# Transient_tester_r2B1.net
KiCad netlist of a schematic drawn in EAGLE
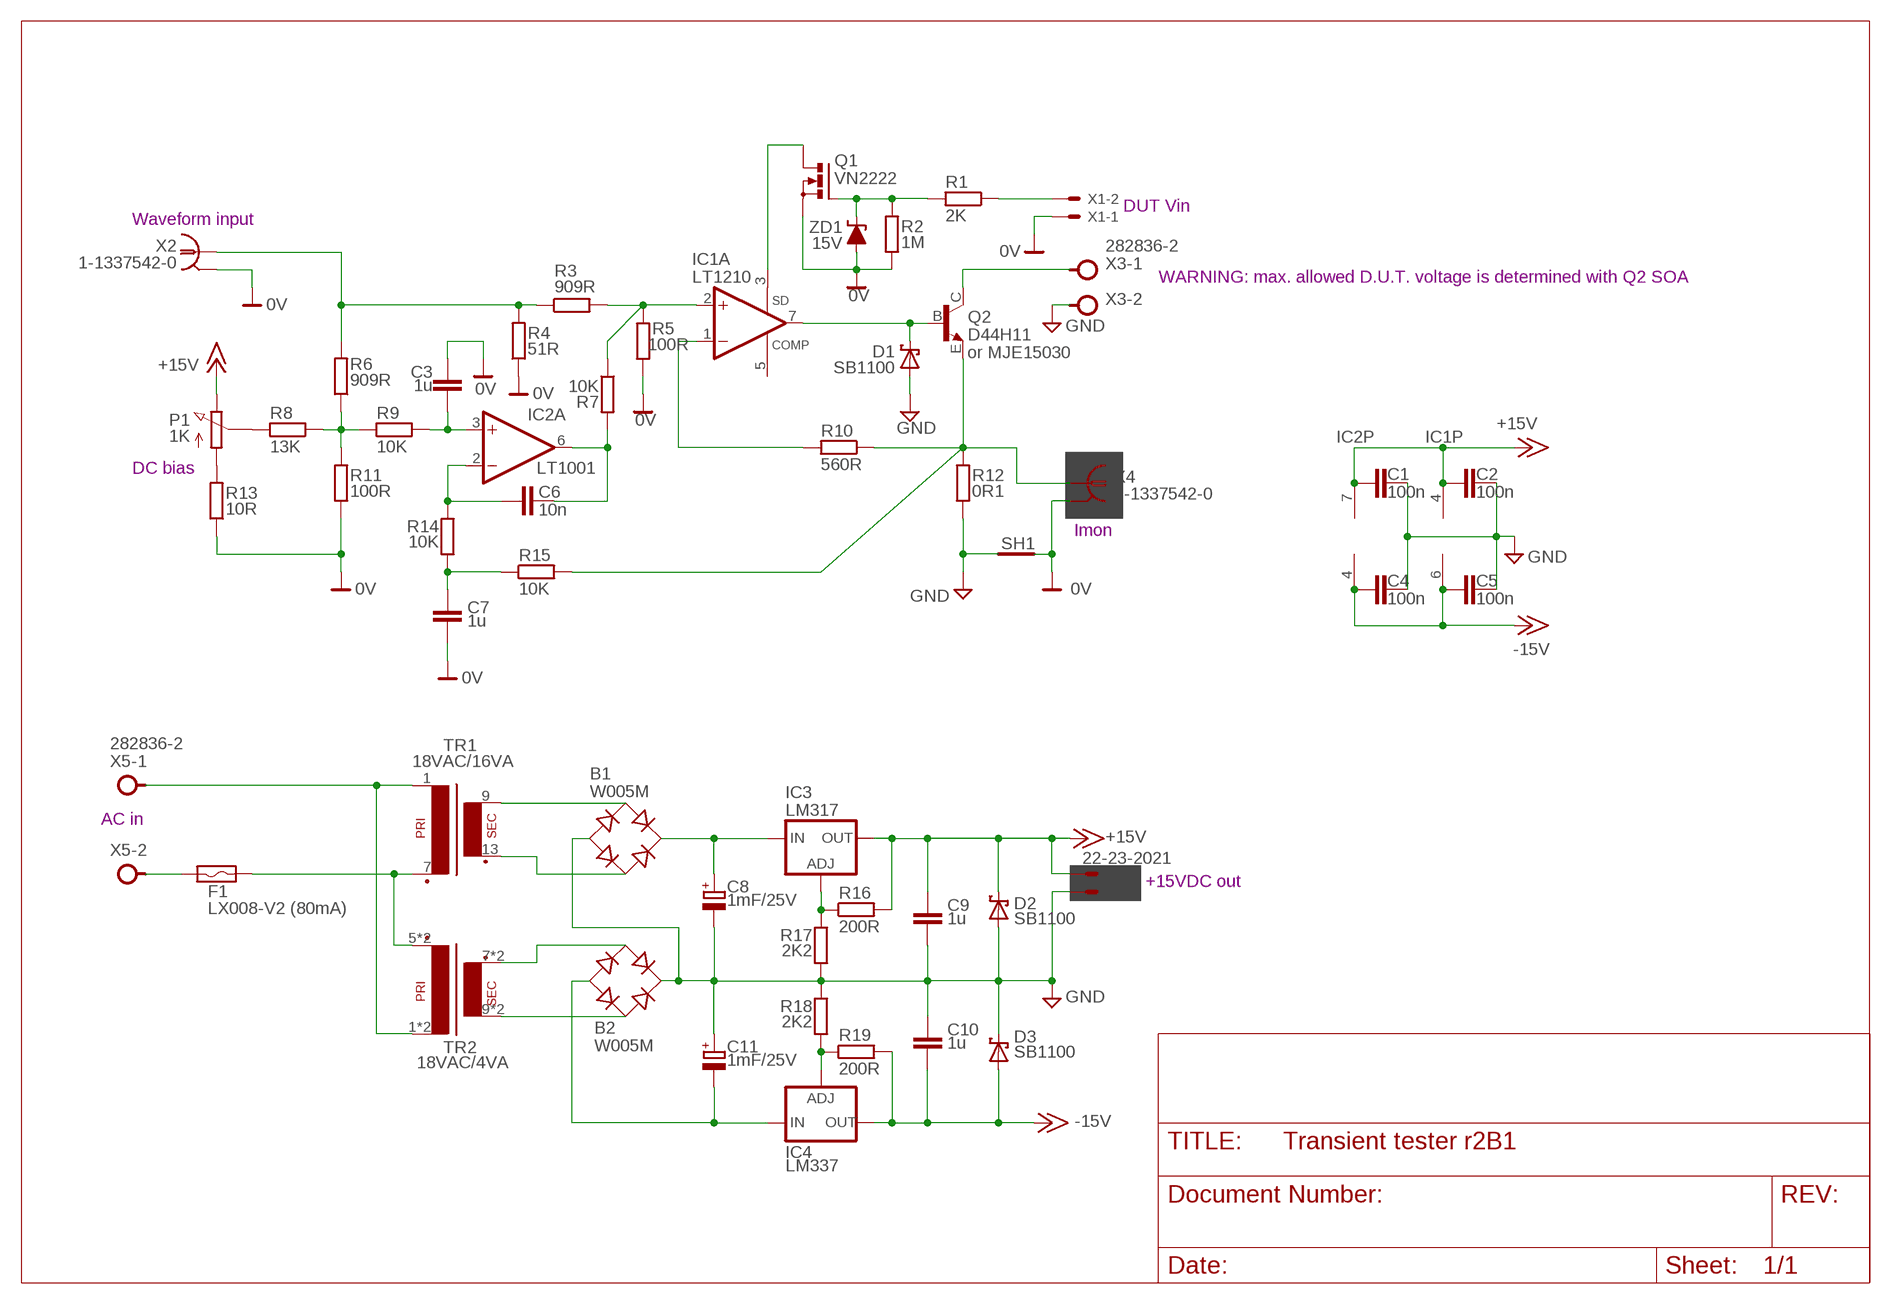
[diagram p0: schematic, sheet 1]

(export (version "E")
  (design (tool "Eeschema 10.0.6"))
  (components
    (comp (ref "B1")
      (value "W005M")
      (footprint "eagle-import:RB1A")
      (libsource (lib "eagle-import") (part "RECTIFIER-RB1A"))
    )
    (comp (ref "B2")
      (value "W005M")
      (footprint "eagle-import:RB1A")
      (libsource (lib "eagle-import") (part "RECTIFIER-RB1A"))
    )
    (comp (ref "C1")
      (value "100n")
      (footprint "eagle-import:C050-025X075")
      (libsource (lib "eagle-import") (part "C-EU050-025X075"))
    )
    (comp (ref "C2")
      (value "100n")
      (footprint "eagle-import:C050-025X075")
      (libsource (lib "eagle-import") (part "C-EU050-025X075"))
    )
    (comp (ref "C3")
      (value "1u")
      (footprint "eagle-import:C050-075X075")
      (libsource (lib "eagle-import") (part "C-EU050-075X075"))
    )
    (comp (ref "C4")
      (value "100n")
      (footprint "eagle-import:C050-025X075")
      (libsource (lib "eagle-import") (part "C-EU050-025X075"))
    )
    (comp (ref "C5")
      (value "100n")
      (footprint "eagle-import:C050-025X075")
      (libsource (lib "eagle-import") (part "C-EU050-025X075"))
    )
    (comp (ref "C6")
      (value "10n")
      (footprint "eagle-import:C050-025X075")
      (libsource (lib "eagle-import") (part "C-EU050-025X075"))
    )
    (comp (ref "C7")
      (value "1u")
      (footprint "eagle-import:C050-075X075")
      (libsource (lib "eagle-import") (part "C-EU050-075X075"))
    )
    (comp (ref "C8")
      (value "1mF/25V")
      (footprint "eagle-import:ECAP5_10.5")
      (libsource (lib "eagle-import") (part "ECAP5G_10.5MM"))
    )
    (comp (ref "C9")
      (value "1u")
      (footprint "eagle-import:C050-025X075")
      (libsource (lib "eagle-import") (part "C-EU050-025X075"))
    )
    (comp (ref "C10")
      (value "1u")
      (footprint "eagle-import:C050-025X075")
      (libsource (lib "eagle-import") (part "C-EU050-025X075"))
    )
    (comp (ref "C11")
      (value "1mF/25V")
      (footprint "eagle-import:ECAP5_10.5")
      (libsource (lib "eagle-import") (part "ECAP5G_10.5MM"))
    )
    (comp (ref "D1")
      (value "SB1100")
      (footprint "eagle-import:DO34_10")
      (libsource (lib "eagle-import") (part "SCHOTTKY"))
    )
    (comp (ref "D2")
      (value "SB1100")
      (footprint "eagle-import:DO34_10")
      (libsource (lib "eagle-import") (part "SCHOTTKY"))
    )
    (comp (ref "D3")
      (value "SB1100")
      (footprint "eagle-import:DO34_10")
      (libsource (lib "eagle-import") (part "SCHOTTKY"))
    )
    (comp (ref "F1")
      (value "LX008-V2 (80mA)")
      (footprint "eagle-import:POLYSWITCH-R7")
      (libsource (lib "eagle-import") (part "FUSE_RESETTABLER7"))
    )
    (comp (ref "IC1")
      (value "LT1210")
      (footprint "eagle-import:TO220-7")
      (libsource (lib "eagle-import") (part "LT1210"))
    )
    (comp (ref "IC2")
      (value "LT1001")
      (footprint "eagle-import:DIL08D")
      (libsource (lib "eagle-import") (part "LT1001"))
    )
    (comp (ref "IC3")
      (value "LM317")
      (footprint "eagle-import:317TS")
      (libsource (lib "eagle-import") (part "LM317TS"))
    )
    (comp (ref "IC4")
      (value "LM337")
      (footprint "eagle-import:337TS")
      (libsource (lib "eagle-import") (part "LM337TS"))
    )
    (comp (ref "P1")
      (value "1K")
      (footprint "eagle-import:BOURNS_POT91")
      (libsource (lib "eagle-import") (part "POTENTIOMETER"))
    )
    (comp (ref "Q1")
      (value "VN2222")
      (footprint "eagle-import:TO92-SGD")
      (libsource (lib "eagle-import") (part "2N7000"))
    )
    (comp (ref "Q2")
      (value "D44H11")
      (footprint "eagle-import:TO220BV")
      (libsource (lib "eagle-import") (part "D44H11"))
    )
    (comp (ref "R1")
      (value "2K")
      (footprint "eagle-import:0204_5")
      (libsource (lib "eagle-import") (part "R-EU_0204/5"))
    )
    (comp (ref "R2")
      (value "1M")
      (footprint "eagle-import:0204_5")
      (libsource (lib "eagle-import") (part "R-EU_0204/5"))
    )
    (comp (ref "R3")
      (value "909R")
      (footprint "eagle-import:0207_10")
      (libsource (lib "eagle-import") (part "R-EU_0207/10"))
    )
    (comp (ref "R4")
      (value "51R")
      (footprint "eagle-import:0204_5")
      (libsource (lib "eagle-import") (part "R-EU_0204/5"))
    )
    (comp (ref "R5")
      (value "100R")
      (footprint "eagle-import:0204_5")
      (libsource (lib "eagle-import") (part "R-EU_0204/5"))
    )
    (comp (ref "R6")
      (value "909R")
      (footprint "eagle-import:0207_10")
      (libsource (lib "eagle-import") (part "R-EU_0207/10"))
    )
    (comp (ref "R7")
      (value "10K")
      (footprint "eagle-import:0204_5")
      (libsource (lib "eagle-import") (part "R-EU_0204/5"))
    )
    (comp (ref "R8")
      (value "13K")
      (footprint "eagle-import:0204_5")
      (libsource (lib "eagle-import") (part "R-EU_0204/5"))
    )
    (comp (ref "R9")
      (value "10K")
      (footprint "eagle-import:0204_5")
      (libsource (lib "eagle-import") (part "R-EU_0204/5"))
    )
    (comp (ref "R10")
      (value "560R")
      (footprint "eagle-import:0204_5")
      (libsource (lib "eagle-import") (part "R-EU_0204/5"))
    )
    (comp (ref "R11")
      (value "100R")
      (footprint "eagle-import:0204_5")
      (libsource (lib "eagle-import") (part "R-EU_0204/5"))
    )
    (comp (ref "R12")
      (value "0R1")
      (footprint "eagle-import:OAR1+2512")
      (libsource (lib "eagle-import") (part "R_EU_OAR1+2512"))
    )
    (comp (ref "R13")
      (value "10R")
      (footprint "eagle-import:0204_5")
      (libsource (lib "eagle-import") (part "R-EU_0204/5"))
    )
    (comp (ref "R14")
      (value "10K")
      (footprint "eagle-import:0204_5")
      (libsource (lib "eagle-import") (part "R-EU_0204/5"))
    )
    (comp (ref "R15")
      (value "10K")
      (footprint "eagle-import:0204_5")
      (libsource (lib "eagle-import") (part "R-EU_0204/5"))
    )
    (comp (ref "R16")
      (value "200R")
      (footprint "eagle-import:0204_5")
      (libsource (lib "eagle-import") (part "R-EU_0204/5"))
    )
    (comp (ref "R17")
      (value "2K2")
      (footprint "eagle-import:0204_5")
      (libsource (lib "eagle-import") (part "R-EU_0204/5"))
    )
    (comp (ref "R18")
      (value "2K2")
      (footprint "eagle-import:0204_5")
      (libsource (lib "eagle-import") (part "R-EU_0204/5"))
    )
    (comp (ref "R19")
      (value "200R")
      (footprint "eagle-import:0204_5")
      (libsource (lib "eagle-import") (part "R-EU_0204/5"))
    )
    (comp (ref "SH1")
      (value "SHORTH")
      (footprint "eagle-import:SHORT_2")
      (libsource (lib "eagle-import") (part "SHORTH"))
    )
    (comp (ref "TR1")
      (value "18VAC/16VA")
      (footprint "eagle-import:PCB_TRAFO16VA")
      (libsource (lib "eagle-import") (part "PCB_TRAFO16VA"))
    )
    (comp (ref "TR2")
      (value "18VAC/4VA")
      (footprint "eagle-import:PCB_TRAFO_4VA")
      (libsource (lib "eagle-import") (part "PCB_TRAFO4VA"))
    )
    (comp (ref "X1")
      (value "22-23-2021")
      (footprint "eagle-import:22-23-2021")
      (fields (field (name "MF") "MOLEX"))
      (libsource (lib "eagle-import") (part "22-23-2021"))
    )
    (comp (ref "X2")
      (value "1-1337542-0")
      (footprint "eagle-import:AMP_227161")
      (fields (field (name "MF") "TYCO ELECTRONICS") (field (name "MPN") "1-227161"))
      (libsource (lib "eagle-import") (part "?2271611--0"))
    )
    (comp (ref "X3")
      (value "282836-2")
      (footprint "eagle-import:TBLOCK5.0_2")
      (libsource (lib "eagle-import") (part "TBLOCK5.0_2A"))
    )
    (comp (ref "X4")
      (value "1-1337542-0")
      (footprint "eagle-import:AMP_227161")
      (fields (field (name "MF") "TYCO ELECTRONICS") (field (name "MPN") "1-227161"))
      (libsource (lib "eagle-import") (part "?2271611--0"))
    )
    (comp (ref "X5")
      (value "282836-2")
      (footprint "eagle-import:TBLOCK5.0_2")
      (libsource (lib "eagle-import") (part "TBLOCK5.0_2A"))
    )
    (comp (ref "X6")
      (value "22-23-2021")
      (footprint "eagle-import:22-23-2021")
      (fields
        (field (name "MF") "MOLEX")
        (field (name "MF_1") "MOLEX")
        (field (name "MPN") "22-23-2021")
        (field (name "OC_FARNELL") "1462926")
        (field (name "OC_NEWARK") "25C3832")
      )
      (libsource (lib "eagle-import") (part "22-23-2021"))
    )
    (comp (ref "ZD1")
      (value "15V")
      (footprint "eagle-import:DO34-ZD")
      (libsource (lib "eagle-import") (part "ZENER-DIODE"))
    )
  )
  (nets
    (net (code "1") (name "+15V") (class "Default")
      (node (ref "C1") (pin "2") (pinfunction "2_2") (pintype "passive"))
      (node (ref "C2") (pin "2") (pinfunction "2_2") (pintype "passive"))
      (node (ref "C9") (pin "1") (pinfunction "1_1") (pintype "passive"))
      (node (ref "D2") (pin "C") (pinfunction "C_C") (pintype "passive"))
      (node (ref "IC1") (pin "4") (pinfunction "V+_4") (pintype "power_in"))
      (node (ref "IC2") (pin "7") (pinfunction "V+_7") (pintype "power_in"))
      (node (ref "IC3") (pin "2") (pinfunction "OUT_2") (pintype "passive"))
      (node (ref "P1") (pin "1") (pinfunction "E_1") (pintype "passive"))
      (node (ref "R16") (pin "2") (pinfunction "2_2") (pintype "passive"))
      (node (ref "X6") (pin "1") (pinfunction "S_1") (pintype "passive"))
    )
    (net (code "2") (name "-15V") (class "Default")
      (node (ref "C10") (pin "2") (pinfunction "2_2") (pintype "passive"))
      (node (ref "C4") (pin "2") (pinfunction "2_2") (pintype "passive"))
      (node (ref "C5") (pin "2") (pinfunction "2_2") (pintype "passive"))
      (node (ref "D3") (pin "A") (pinfunction "A_A") (pintype "passive"))
      (node (ref "IC1") (pin "6") (pinfunction "V-_6") (pintype "power_in"))
      (node (ref "IC2") (pin "4") (pinfunction "V-_4") (pintype "power_in"))
      (node (ref "IC4") (pin "3") (pinfunction "OUT_3") (pintype "passive"))
      (node (ref "R19") (pin "2") (pinfunction "2_2") (pintype "passive"))
    )
    (net (code "3") (name "0V") (class "Default")
      (node (ref "C3") (pin "1") (pinfunction "1_1") (pintype "passive"))
      (node (ref "C7") (pin "2") (pinfunction "2_2") (pintype "passive"))
      (node (ref "Q1") (pin "S") (pinfunction "S_S") (pintype "passive"))
      (node (ref "R11") (pin "1") (pinfunction "1_1") (pintype "passive"))
      (node (ref "R13") (pin "1") (pinfunction "1_1") (pintype "passive"))
      (node (ref "R2") (pin "1") (pinfunction "1_1") (pintype "passive"))
      (node (ref "R4") (pin "1") (pinfunction "1_1") (pintype "passive"))
      (node (ref "R5") (pin "2") (pinfunction "2_2") (pintype "passive"))
      (node (ref "SH1") (pin "2") (pinfunction "GND_B_2") (pintype "bidirectional"))
      (node (ref "X1") (pin "1") (pinfunction "S_1") (pintype "passive"))
      (node (ref "X2") (pin "2") (pinfunction "GND_2") (pintype "power_in"))
      (node (ref "X4") (pin "2") (pinfunction "GND_2") (pintype "power_in"))
      (node (ref "ZD1") (pin "A") (pinfunction "A_A") (pintype "passive"))
    )
    (net (code "4") (name "GND") (class "Default")
      (node (ref "B1") (pin "-") (pinfunction "-_-") (pintype "passive"))
      (node (ref "B2") (pin "+") (pinfunction "+_+") (pintype "passive"))
      (node (ref "C1") (pin "1") (pinfunction "1_1") (pintype "passive"))
      (node (ref "C10") (pin "1") (pinfunction "1_1") (pintype "passive"))
      (node (ref "C11") (pin "+") (pinfunction "+_+") (pintype "passive"))
      (node (ref "C2") (pin "1") (pinfunction "1_1") (pintype "passive"))
      (node (ref "C4") (pin "1") (pinfunction "1_1") (pintype "passive"))
      (node (ref "C5") (pin "1") (pinfunction "1_1") (pintype "passive"))
      (node (ref "C8") (pin "-") (pinfunction "-_-") (pintype "passive"))
      (node (ref "C9") (pin "2") (pinfunction "2_2") (pintype "passive"))
      (node (ref "D1") (pin "A") (pinfunction "A_A") (pintype "passive"))
      (node (ref "D2") (pin "A") (pinfunction "A_A") (pintype "passive"))
      (node (ref "D3") (pin "C") (pinfunction "C_C") (pintype "passive"))
      (node (ref "R12") (pin "1") (pinfunction "1_1") (pintype "passive"))
      (node (ref "R12") (pin "1.1") (pinfunction "1_1.1") (pintype "passive"))
      (node (ref "R17") (pin "2") (pinfunction "2_2") (pintype "passive"))
      (node (ref "R18") (pin "1") (pinfunction "1_1") (pintype "passive"))
      (node (ref "SH1") (pin "1") (pinfunction "GND_A_1") (pintype "bidirectional"))
      (node (ref "X3") (pin "2") (pinfunction "1_2") (pintype "bidirectional"))
      (node (ref "X6") (pin "2") (pinfunction "S_2") (pintype "passive"))
    )
    (net (code "5") (name "Net-(B2-PadAC1)") (class "Default")
      (node (ref "B2") (pin "AC1") (pinfunction "AC1_AC1") (pintype "passive"))
      (node (ref "TR2") (pin "7") (pinfunction "S2_7") (pintype "passive"))
      (node (ref "TR2") (pin "7.1") (pinfunction "S2_7.1") (pintype "passive"))
    )
    (net (code "6") (name "Net-(B2-PadAC2)") (class "Default")
      (node (ref "B2") (pin "AC2") (pinfunction "AC2_AC2") (pintype "passive"))
      (node (ref "TR2") (pin "9") (pinfunction "S1_9") (pintype "passive"))
      (node (ref "TR2") (pin "9.1") (pinfunction "S1_9.1") (pintype "passive"))
    )
    (net (code "7") (name "Net-(C7-Pad1)") (class "Default")
      (node (ref "C7") (pin "1") (pinfunction "1_1") (pintype "passive"))
      (node (ref "R14") (pin "2") (pinfunction "2_2") (pintype "passive"))
      (node (ref "R15") (pin "1") (pinfunction "1_1") (pintype "passive"))
    )
    (net (code "8") (name "Net-(F1-1)") (class "Default")
      (node (ref "F1") (pin "P$1") (pinfunction "1_P$1") (pintype "passive"))
      (node (ref "X5") (pin "2") (pinfunction "1_2") (pintype "bidirectional"))
    )
    (net (code "9") (name "Net-(F1-2)") (class "Default")
      (node (ref "F1") (pin "P$2") (pinfunction "2_P$2") (pintype "passive"))
      (node (ref "TR1") (pin "7") (pinfunction "P2_7") (pintype "passive"))
      (node (ref "TR2") (pin "5") (pinfunction "P2_5") (pintype "passive"))
      (node (ref "TR2") (pin "5.1") (pinfunction "P2_5.1") (pintype "passive"))
    )
    (net (code "10") (name "Net-(IC1A-+IN)") (class "Default")
      (node (ref "IC1") (pin "2") (pinfunction "+IN_2") (pintype "input"))
      (node (ref "R3") (pin "2") (pinfunction "2_2") (pintype "passive"))
      (node (ref "R5") (pin "1") (pinfunction "1_1") (pintype "passive"))
      (node (ref "R7") (pin "1") (pinfunction "1_1") (pintype "passive"))
    )
    (net (code "11") (name "Net-(IC1A--IN)") (class "Default")
      (node (ref "IC1") (pin "1") (pinfunction "-IN_1") (pintype "input"))
      (node (ref "R10") (pin "2") (pinfunction "2_2") (pintype "passive"))
    )
    (net (code "12") (name "Net-(IC1A-OUT)") (class "Default")
      (node (ref "D1") (pin "C") (pinfunction "C_C") (pintype "passive"))
      (node (ref "IC1") (pin "7") (pinfunction "OUT_7") (pintype "output"))
      (node (ref "Q2") (pin "B") (pinfunction "B_B") (pintype "passive"))
    )
    (net (code "13") (name "Net-(IC1A-SD)") (class "Default")
      (node (ref "IC1") (pin "3") (pinfunction "SD_3") (pintype "input"))
      (node (ref "Q1") (pin "D") (pinfunction "D_D") (pintype "passive"))
    )
    (net (code "14") (name "Net-(IC2A-+IN)") (class "Default")
      (node (ref "C3") (pin "2") (pinfunction "2_2") (pintype "passive"))
      (node (ref "IC2") (pin "3") (pinfunction "+IN_3") (pintype "input"))
      (node (ref "R9") (pin "2") (pinfunction "2_2") (pintype "passive"))
    )
    (net (code "15") (name "Net-(IC2A--IN)") (class "Default")
      (node (ref "C6") (pin "2") (pinfunction "2_2") (pintype "passive"))
      (node (ref "IC2") (pin "2") (pinfunction "-IN_2") (pintype "input"))
      (node (ref "R14") (pin "1") (pinfunction "1_1") (pintype "passive"))
    )
    (net (code "16") (name "Net-(IC2A-OUT)") (class "Default")
      (node (ref "C6") (pin "1") (pinfunction "1_1") (pintype "passive"))
      (node (ref "IC2") (pin "6") (pinfunction "OUT_6") (pintype "output"))
      (node (ref "R7") (pin "2") (pinfunction "2_2") (pintype "passive"))
    )
    (net (code "17") (name "Net-(IC3-ADJ)") (class "Default")
      (node (ref "IC3") (pin "1") (pinfunction "ADJ_1") (pintype "input"))
      (node (ref "R16") (pin "1") (pinfunction "1_1") (pintype "passive"))
      (node (ref "R17") (pin "1") (pinfunction "1_1") (pintype "passive"))
    )
    (net (code "18") (name "Net-(IC3-IN)") (class "Default")
      (node (ref "B1") (pin "+") (pinfunction "+_+") (pintype "passive"))
      (node (ref "C8") (pin "+") (pinfunction "+_+") (pintype "passive"))
      (node (ref "IC3") (pin "3") (pinfunction "IN_3") (pintype "input"))
    )
    (net (code "19") (name "Net-(IC4-ADJ)") (class "Default")
      (node (ref "IC4") (pin "1") (pinfunction "ADJ_1") (pintype "input"))
      (node (ref "R18") (pin "2") (pinfunction "2_2") (pintype "passive"))
      (node (ref "R19") (pin "1") (pinfunction "1_1") (pintype "passive"))
    )
    (net (code "20") (name "Net-(IC4-IN)") (class "Default")
      (node (ref "B2") (pin "-") (pinfunction "-_-") (pintype "passive"))
      (node (ref "C11") (pin "-") (pinfunction "-_-") (pintype "passive"))
      (node (ref "IC4") (pin "2") (pinfunction "IN_2") (pintype "input"))
    )
    (net (code "21") (name "Net-(P1-A)") (class "Default")
      (node (ref "P1") (pin "3") (pinfunction "A_3") (pintype "passive"))
      (node (ref "R13") (pin "2") (pinfunction "2_2") (pintype "passive"))
    )
    (net (code "22") (name "Net-(P1-S)") (class "Default")
      (node (ref "P1") (pin "2") (pinfunction "S_2") (pintype "passive"))
      (node (ref "R8") (pin "2") (pinfunction "2_2") (pintype "passive"))
    )
    (net (code "23") (name "Net-(Q1-PadG)") (class "Default")
      (node (ref "Q1") (pin "G") (pinfunction "G_G") (pintype "passive"))
      (node (ref "R1") (pin "2") (pinfunction "2_2") (pintype "passive"))
      (node (ref "R2") (pin "2") (pinfunction "2_2") (pintype "passive"))
      (node (ref "ZD1") (pin "C") (pinfunction "C_C") (pintype "passive"))
    )
    (net (code "24") (name "Net-(Q2-PadC)") (class "Default")
      (node (ref "Q2") (pin "C") (pinfunction "C_C") (pintype "passive"))
      (node (ref "X3") (pin "1") (pinfunction "1_1") (pintype "bidirectional"))
    )
    (net (code "25") (name "Net-(Q2-PadE)") (class "Default")
      (node (ref "Q2") (pin "E") (pinfunction "E_E") (pintype "passive"))
      (node (ref "R10") (pin "1") (pinfunction "1_1") (pintype "passive"))
      (node (ref "R12") (pin "2") (pinfunction "2_2") (pintype "passive"))
      (node (ref "R12") (pin "2.1") (pinfunction "2_2.1") (pintype "passive"))
      (node (ref "R15") (pin "2") (pinfunction "2_2") (pintype "passive"))
      (node (ref "X4") (pin "1") (pinfunction "1_1") (pintype "passive"))
    )
    (net (code "26") (name "Net-(R3-Pad1)") (class "Default")
      (node (ref "R3") (pin "1") (pinfunction "1_1") (pintype "passive"))
      (node (ref "R4") (pin "2") (pinfunction "2_2") (pintype "passive"))
      (node (ref "R6") (pin "2") (pinfunction "2_2") (pintype "passive"))
      (node (ref "X2") (pin "1") (pinfunction "1_1") (pintype "passive"))
    )
    (net (code "27") (name "Net-(R11-Pad2)") (class "Default")
      (node (ref "R11") (pin "2") (pinfunction "2_2") (pintype "passive"))
      (node (ref "R6") (pin "1") (pinfunction "1_1") (pintype "passive"))
      (node (ref "R8") (pin "1") (pinfunction "1_1") (pintype "passive"))
      (node (ref "R9") (pin "1") (pinfunction "1_1") (pintype "passive"))
    )
    (net (code "28") (name "Net-(TR1-P1)") (class "Default")
      (node (ref "TR1") (pin "1") (pinfunction "P1_1") (pintype "passive"))
      (node (ref "TR2") (pin "1") (pinfunction "P1_1") (pintype "passive"))
      (node (ref "TR2") (pin "1.1") (pinfunction "P1_1.1") (pintype "passive"))
      (node (ref "X5") (pin "1") (pinfunction "1_1") (pintype "bidirectional"))
    )
    (net (code "29") (name "Net-(TR1-S1)") (class "Default")
      (node (ref "B1") (pin "AC2") (pinfunction "AC2_AC2") (pintype "passive"))
      (node (ref "TR1") (pin "9") (pinfunction "S1_9") (pintype "passive"))
    )
    (net (code "30") (name "Net-(TR1-S2)") (class "Default")
      (node (ref "B1") (pin "AC1") (pinfunction "AC1_AC1") (pintype "passive"))
      (node (ref "TR1") (pin "13") (pinfunction "S2_13") (pintype "passive"))
    )
    (net (code "31") (name "Net-(X1B-S)") (class "Default")
      (node (ref "R1") (pin "1") (pinfunction "1_1") (pintype "passive"))
      (node (ref "X1") (pin "2") (pinfunction "S_2") (pintype "passive"))
    )
    (net (code "32") (name "unconnected-(IC1A-COMP-Pad5)") (class "Default")
      (node (ref "IC1") (pin "5") (pinfunction "COMP_5") (pintype "input"))
    )
  )
)
